# PFC_nano_breakout.net
KiCad netlist of a schematic drawn in EAGLE
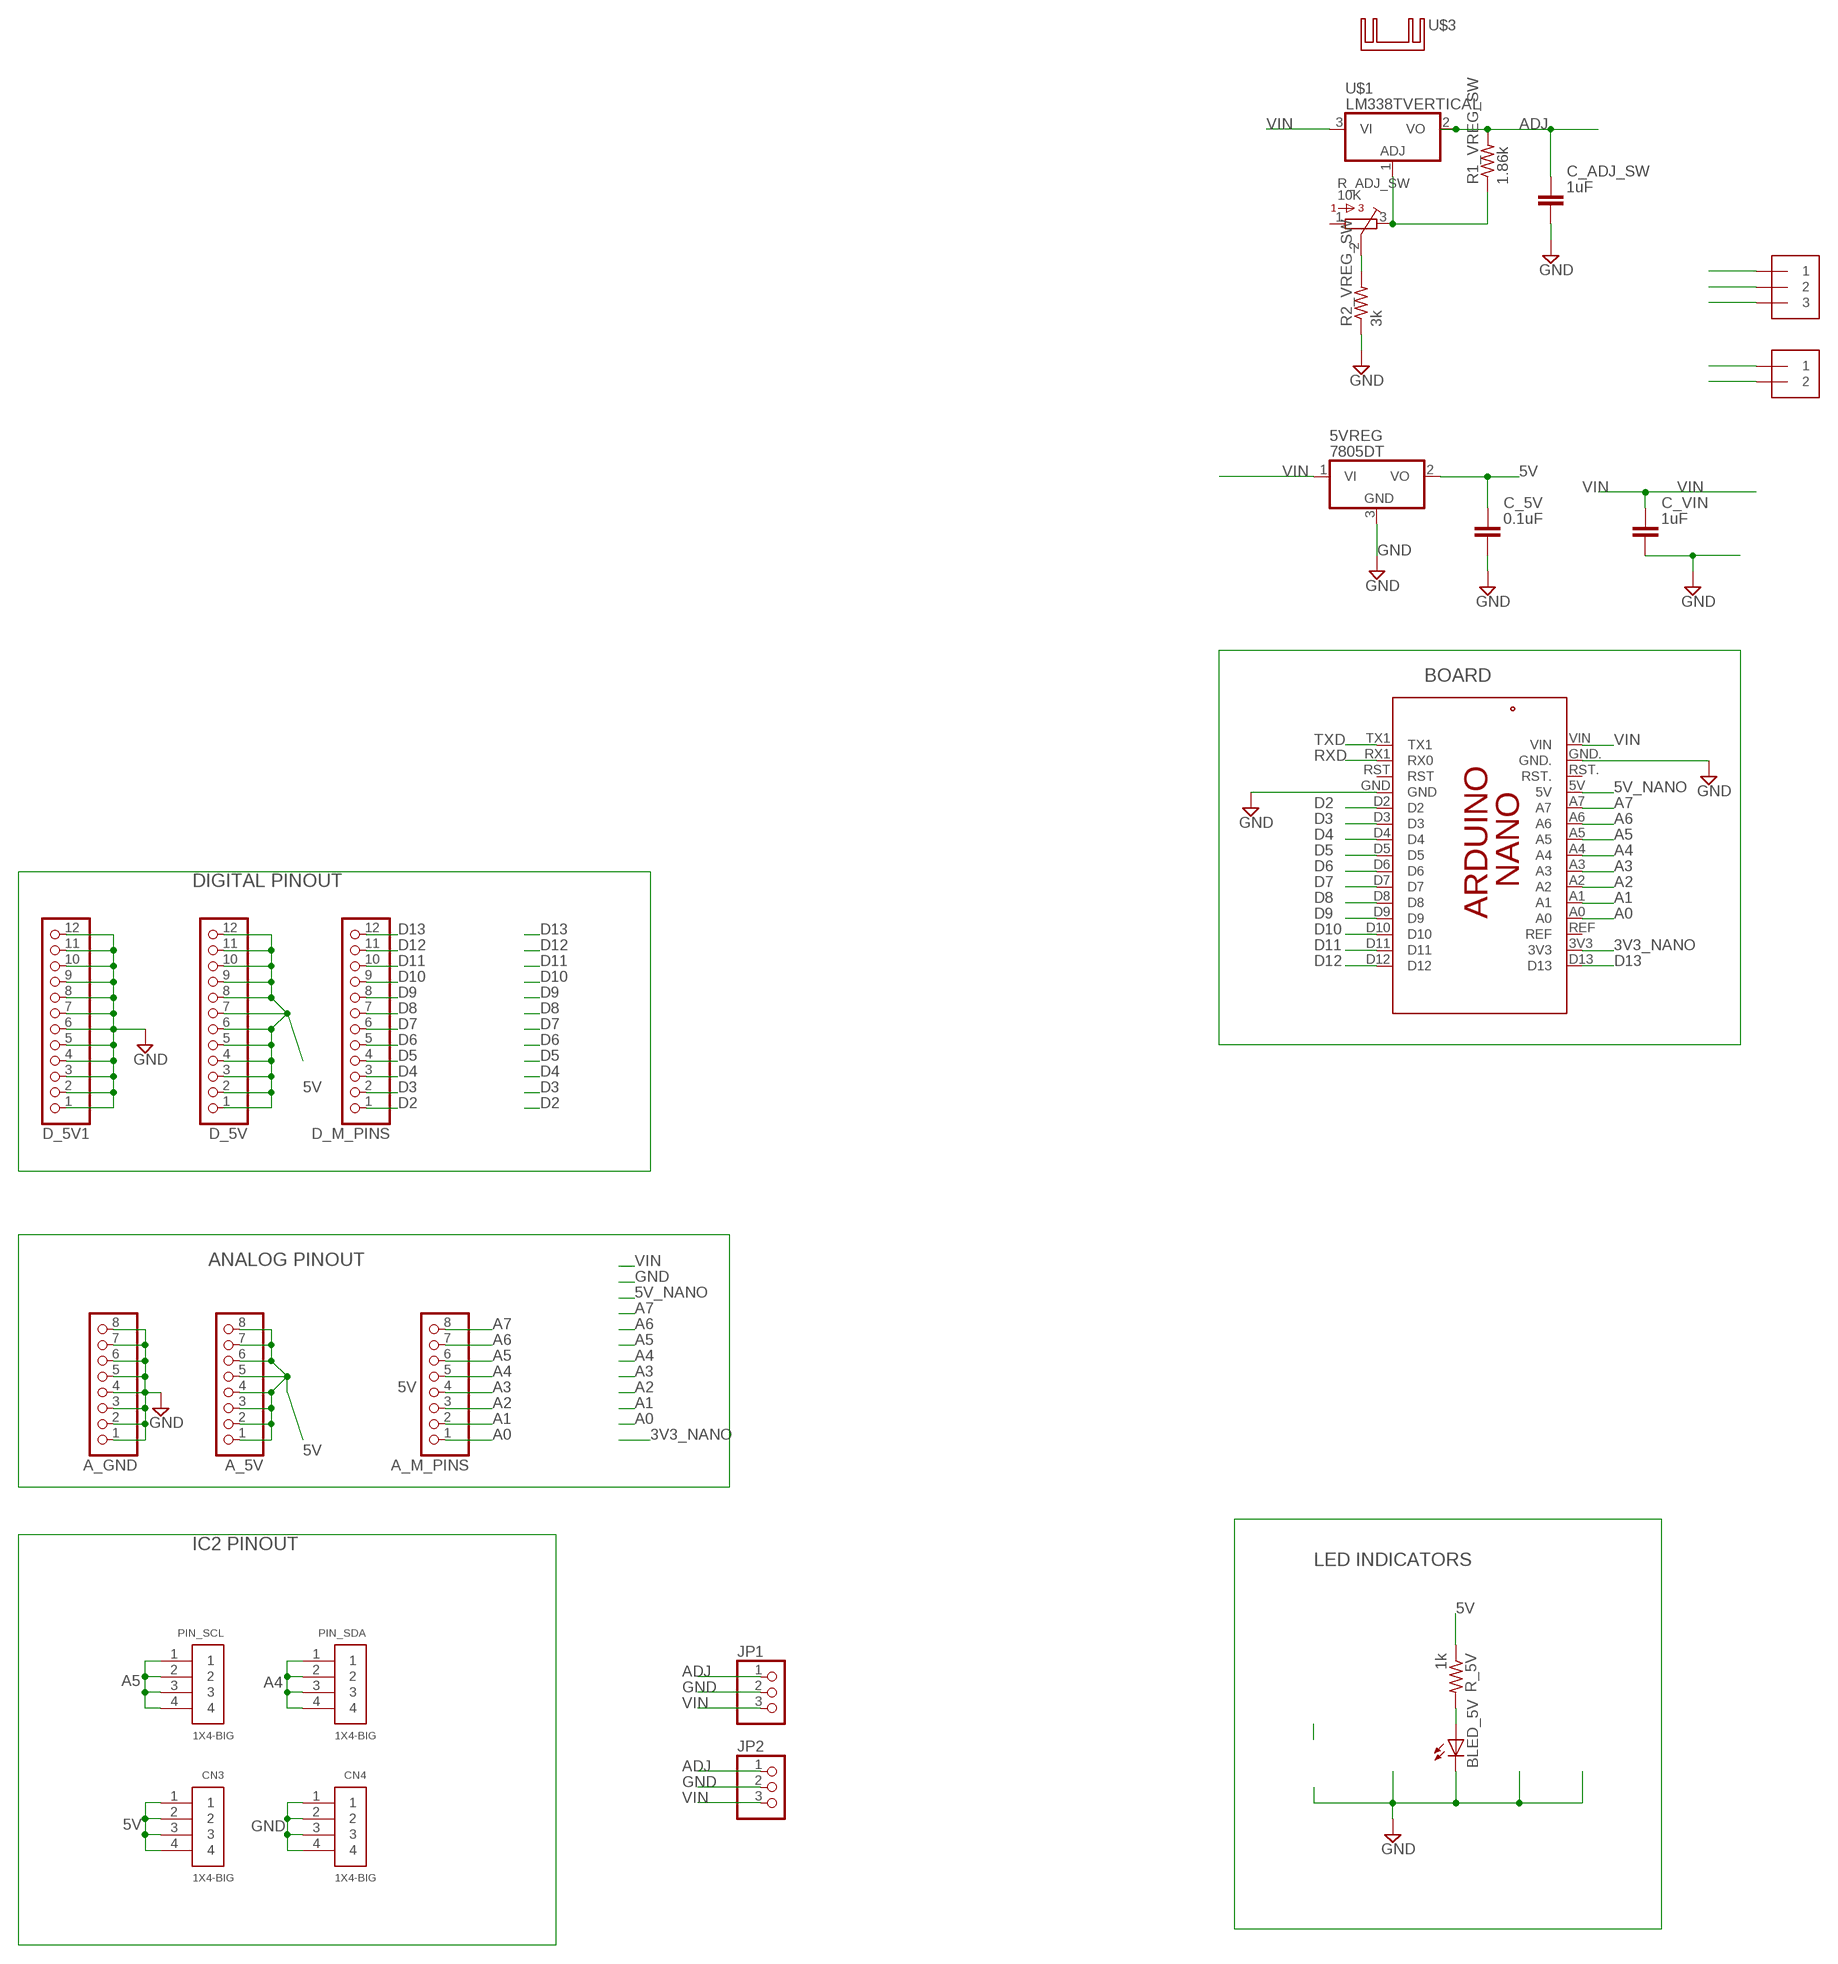
[diagram p0: schematic, sheet 1]

(export (version "E")
  (design (tool "Eeschema 10.0.6"))
  (components
    (comp (ref "5VREG")
      (value "7805DT")
      (footprint "eagle-import:TO252")
      (libsource (lib "eagle-import") (part "78DT05"))
    )
    (comp (ref "A_5V")
      (value "PINHD-1X8CLEANBIG")
      (footprint "eagle-import:1X08-CLEANBIG")
      (libsource (lib "eagle-import") (part "PINHD-1X8CLEANBIG"))
    )
    (comp (ref "A_GND")
      (value "PINHD-1X8CLEANBIG")
      (footprint "eagle-import:1X08-CLEANBIG")
      (libsource (lib "eagle-import") (part "PINHD-1X8CLEANBIG"))
    )
    (comp (ref "A_M_PINS")
      (value "PINHD-1X8CLEANBIG")
      (footprint "eagle-import:1X08-CLEANBIG")
      (libsource (lib "eagle-import") (part "PINHD-1X8CLEANBIG"))
    )
    (comp (ref "BLED_5V")
      (value "LEDCHIP-LED0603")
      (footprint "eagle-import:CHIP-LED0603")
      (libsource (lib "eagle-import") (part "LEDCHIP-LED0603"))
    )
    (comp (ref "CN3")
      (value "1X4-BIG")
      (footprint "eagle-import:1X04-BIG")
      (libsource (lib "eagle-import") (part "1X4-BIG"))
    )
    (comp (ref "CN4")
      (value "1X4-BIG")
      (footprint "eagle-import:1X04-BIG")
      (libsource (lib "eagle-import") (part "1X4-BIG"))
    )
    (comp (ref "C_5V")
      (value "0.1uF")
      (footprint "eagle-import:C603")
      (libsource (lib "eagle-import") (part "CAPACITOR_NPOL-0603"))
    )
    (comp (ref "C_ADJ_SW")
      (value "1uF")
      (footprint "eagle-import:C603")
      (libsource (lib "eagle-import") (part "CAPACITOR_NPOL-0603"))
    )
    (comp (ref "C_VIN")
      (value "1uF")
      (footprint "eagle-import:C603")
      (libsource (lib "eagle-import") (part "CAPACITOR_NPOL-0603"))
    )
    (comp (ref "D_5V")
      (value "PINHD-1X12-CB")
      (footprint "eagle-import:1X12-CB")
      (libsource (lib "eagle-import") (part "PINHD-1X12-CB"))
    )
    (comp (ref "D_5V1")
      (value "PINHD-1X12-CB")
      (footprint "eagle-import:1X12-CB")
      (libsource (lib "eagle-import") (part "PINHD-1X12-CB"))
    )
    (comp (ref "D_M_PINS")
      (value "PINHD-1X12-CB")
      (footprint "eagle-import:1X12-CB")
      (libsource (lib "eagle-import") (part "PINHD-1X12-CB"))
    )
    (comp (ref "J2")
      (value "1X2-3.5MM")
      (footprint "eagle-import:1X2-3.5MM")
      (libsource (lib "eagle-import") (part "1X2-3.5MM"))
    )
    (comp (ref "JP1")
      (value "PINHD-1X3CB")
      (footprint "eagle-import:1X03-CLEANBIG")
      (libsource (lib "eagle-import") (part "PINHD-1X3CB"))
    )
    (comp (ref "JP2")
      (value "PINHD-1X3CB")
      (footprint "eagle-import:1X03-CLEANBIG")
      (libsource (lib "eagle-import") (part "PINHD-1X3CB"))
    )
    (comp (ref "PCB1")
      (value "ARDUINO_NANO_SHIELD")
      (footprint "eagle-import:ARDUINO_NANO_SHIELD")
      (libsource (lib "eagle-import") (part "ARDUINO_NANO_SHIELD"))
    )
    (comp (ref "PIN_SCL")
      (value "1X4-BIG")
      (footprint "eagle-import:1X04-BIG")
      (libsource (lib "eagle-import") (part "1X4-BIG"))
    )
    (comp (ref "PIN_SDA")
      (value "1X4-BIG")
      (footprint "eagle-import:1X04-BIG")
      (libsource (lib "eagle-import") (part "1X4-BIG"))
    )
    (comp (ref "R1_VREG_SW")
      (value "1.86k")
      (footprint "eagle-import:R0603")
      (libsource (lib "eagle-import") (part "R-US_R0603"))
    )
    (comp (ref "R2_VREG_SW")
      (value "3k")
      (footprint "eagle-import:R0603")
      (libsource (lib "eagle-import") (part "R-US_R0603"))
    )
    (comp (ref "R_5V")
      (value "1k")
      (footprint "eagle-import:R0603")
      (libsource (lib "eagle-import") (part "R-US_R0603"))
    )
    (comp (ref "R_ADJ_SW")
      (value "10K")
      (footprint "eagle-import:3386P")
      (libsource (lib "eagle-import") (part "3386-P"))
    )
    (comp (ref "U$1")
      (value "LM338TVERTICAL")
      (footprint "eagle-import:TO220V")
      (libsource (lib "eagle-import") (part "LM338TVERTICAL"))
    )
    (comp (ref "U$2")
      (value "1X3")
      (footprint "eagle-import:1X3-3.5MM")
      (libsource (lib "eagle-import") (part "1X3"))
    )
    (comp (ref "U$3")
      (value "FW1S")
      (footprint "eagle-import:FW1S-DOCU")
      (libsource (lib "eagle-import") (part "FW1S"))
    )
  )
  (nets
    (net (code "1") (name "/3V3_NANO") (class "Default")
      (node (ref "PCB1") (pin "3V3") (pinfunction "3V3_3V3") (pintype "bidirectional"))
    )
    (net (code "2") (name "/5V") (class "Default")
      (node (ref "5VREG") (pin "2") (pinfunction "VO_2") (pintype "passive"))
      (node (ref "A_5V") (pin "1") (pinfunction "1_1") (pintype "passive"))
      (node (ref "A_5V") (pin "2") (pinfunction "2_2") (pintype "passive"))
      (node (ref "A_5V") (pin "3") (pinfunction "3_3") (pintype "passive"))
      (node (ref "A_5V") (pin "4") (pinfunction "4_4") (pintype "passive"))
      (node (ref "A_5V") (pin "5") (pinfunction "5_5") (pintype "passive"))
      (node (ref "A_5V") (pin "6") (pinfunction "6_6") (pintype "passive"))
      (node (ref "A_5V") (pin "7") (pinfunction "7_7") (pintype "passive"))
      (node (ref "A_5V") (pin "8") (pinfunction "8_8") (pintype "passive"))
      (node (ref "CN3") (pin "1") (pinfunction "1_1") (pintype "bidirectional"))
      (node (ref "CN3") (pin "2") (pinfunction "2_2") (pintype "bidirectional"))
      (node (ref "CN3") (pin "3") (pinfunction "3_3") (pintype "bidirectional"))
      (node (ref "CN3") (pin "4") (pinfunction "4_4") (pintype "bidirectional"))
      (node (ref "C_5V") (pin "1") (pinfunction "1_1") (pintype "passive"))
      (node (ref "D_5V") (pin "1") (pinfunction "1_1") (pintype "passive"))
      (node (ref "D_5V") (pin "10") (pinfunction "10_10") (pintype "passive"))
      (node (ref "D_5V") (pin "11") (pinfunction "11_11") (pintype "passive"))
      (node (ref "D_5V") (pin "12") (pinfunction "12_12") (pintype "passive"))
      (node (ref "D_5V") (pin "2") (pinfunction "2_2") (pintype "passive"))
      (node (ref "D_5V") (pin "3") (pinfunction "3_3") (pintype "passive"))
      (node (ref "D_5V") (pin "4") (pinfunction "4_4") (pintype "passive"))
      (node (ref "D_5V") (pin "5") (pinfunction "5_5") (pintype "passive"))
      (node (ref "D_5V") (pin "6") (pinfunction "6_6") (pintype "passive"))
      (node (ref "D_5V") (pin "7") (pinfunction "7_7") (pintype "passive"))
      (node (ref "D_5V") (pin "8") (pinfunction "8_8") (pintype "passive"))
      (node (ref "D_5V") (pin "9") (pinfunction "9_9") (pintype "passive"))
      (node (ref "R_5V") (pin "1") (pinfunction "1_1") (pintype "passive"))
    )
    (net (code "3") (name "/5V_NANO") (class "Default")
      (node (ref "PCB1") (pin "5V") (pinfunction "5V_5V") (pintype "bidirectional"))
    )
    (net (code "4") (name "/A0") (class "Default")
      (node (ref "A_M_PINS") (pin "1") (pinfunction "1_1") (pintype "passive"))
      (node (ref "PCB1") (pin "A0") (pinfunction "A0_A0") (pintype "bidirectional"))
    )
    (net (code "5") (name "/A1") (class "Default")
      (node (ref "A_M_PINS") (pin "2") (pinfunction "2_2") (pintype "passive"))
      (node (ref "PCB1") (pin "A1") (pinfunction "A1_A1") (pintype "bidirectional"))
    )
    (net (code "6") (name "/A2") (class "Default")
      (node (ref "A_M_PINS") (pin "3") (pinfunction "3_3") (pintype "passive"))
      (node (ref "PCB1") (pin "A2") (pinfunction "A2_A2") (pintype "bidirectional"))
    )
    (net (code "7") (name "/A3") (class "Default")
      (node (ref "A_M_PINS") (pin "4") (pinfunction "4_4") (pintype "passive"))
      (node (ref "PCB1") (pin "A3") (pinfunction "A3_A3") (pintype "bidirectional"))
    )
    (net (code "8") (name "/A4") (class "Default")
      (node (ref "A_M_PINS") (pin "5") (pinfunction "5_5") (pintype "passive"))
      (node (ref "PCB1") (pin "A4") (pinfunction "A4_A4") (pintype "bidirectional"))
      (node (ref "PIN_SDA") (pin "1") (pinfunction "1_1") (pintype "bidirectional"))
      (node (ref "PIN_SDA") (pin "2") (pinfunction "2_2") (pintype "bidirectional"))
      (node (ref "PIN_SDA") (pin "3") (pinfunction "3_3") (pintype "bidirectional"))
      (node (ref "PIN_SDA") (pin "4") (pinfunction "4_4") (pintype "bidirectional"))
    )
    (net (code "9") (name "/A5") (class "Default")
      (node (ref "A_M_PINS") (pin "6") (pinfunction "6_6") (pintype "passive"))
      (node (ref "PCB1") (pin "A5") (pinfunction "A5_A5") (pintype "bidirectional"))
      (node (ref "PIN_SCL") (pin "1") (pinfunction "1_1") (pintype "bidirectional"))
      (node (ref "PIN_SCL") (pin "2") (pinfunction "2_2") (pintype "bidirectional"))
      (node (ref "PIN_SCL") (pin "3") (pinfunction "3_3") (pintype "bidirectional"))
      (node (ref "PIN_SCL") (pin "4") (pinfunction "4_4") (pintype "bidirectional"))
    )
    (net (code "10") (name "/A6") (class "Default")
      (node (ref "A_M_PINS") (pin "7") (pinfunction "7_7") (pintype "passive"))
      (node (ref "PCB1") (pin "A6") (pinfunction "A6_A6") (pintype "bidirectional"))
    )
    (net (code "11") (name "/A7") (class "Default")
      (node (ref "A_M_PINS") (pin "8") (pinfunction "8_8") (pintype "passive"))
      (node (ref "PCB1") (pin "A7") (pinfunction "A7_A7") (pintype "bidirectional"))
    )
    (net (code "12") (name "/ADJ") (class "Default")
      (node (ref "C_ADJ_SW") (pin "1") (pinfunction "1_1") (pintype "passive"))
      (node (ref "JP1") (pin "1") (pinfunction "1_1") (pintype "passive"))
      (node (ref "JP2") (pin "1") (pinfunction "1_1") (pintype "passive"))
      (node (ref "R1_VREG_SW") (pin "2") (pinfunction "2_2") (pintype "passive"))
      (node (ref "U$1") (pin "2") (pinfunction "VO_2") (pintype "passive"))
      (node (ref "U$2") (pin "2") (pinfunction "2_2") (pintype "passive"))
    )
    (net (code "13") (name "/D2") (class "Default")
      (node (ref "D_M_PINS") (pin "1") (pinfunction "1_1") (pintype "passive"))
      (node (ref "PCB1") (pin "D2") (pinfunction "D2_D2") (pintype "bidirectional"))
    )
    (net (code "14") (name "/D3") (class "Default")
      (node (ref "D_M_PINS") (pin "2") (pinfunction "2_2") (pintype "passive"))
      (node (ref "PCB1") (pin "D3") (pinfunction "D3_D3") (pintype "bidirectional"))
    )
    (net (code "15") (name "/D4") (class "Default")
      (node (ref "D_M_PINS") (pin "3") (pinfunction "3_3") (pintype "passive"))
      (node (ref "PCB1") (pin "D4") (pinfunction "D4_D4") (pintype "bidirectional"))
    )
    (net (code "16") (name "/D5") (class "Default")
      (node (ref "D_M_PINS") (pin "4") (pinfunction "4_4") (pintype "passive"))
      (node (ref "PCB1") (pin "D5") (pinfunction "D5_D5") (pintype "bidirectional"))
    )
    (net (code "17") (name "/D6") (class "Default")
      (node (ref "D_M_PINS") (pin "5") (pinfunction "5_5") (pintype "passive"))
      (node (ref "PCB1") (pin "D6") (pinfunction "D6_D6") (pintype "bidirectional"))
    )
    (net (code "18") (name "/D7") (class "Default")
      (node (ref "D_M_PINS") (pin "6") (pinfunction "6_6") (pintype "passive"))
      (node (ref "PCB1") (pin "D7") (pinfunction "D7_D7") (pintype "bidirectional"))
    )
    (net (code "19") (name "/D8") (class "Default")
      (node (ref "D_M_PINS") (pin "7") (pinfunction "7_7") (pintype "passive"))
      (node (ref "PCB1") (pin "D8") (pinfunction "D8_D8") (pintype "bidirectional"))
    )
    (net (code "20") (name "/D9") (class "Default")
      (node (ref "D_M_PINS") (pin "8") (pinfunction "8_8") (pintype "passive"))
      (node (ref "PCB1") (pin "D9") (pinfunction "D9_D9") (pintype "bidirectional"))
    )
    (net (code "21") (name "/D10") (class "Default")
      (node (ref "D_M_PINS") (pin "9") (pinfunction "9_9") (pintype "passive"))
      (node (ref "PCB1") (pin "D10") (pinfunction "D10_D10") (pintype "bidirectional"))
    )
    (net (code "22") (name "/D11") (class "Default")
      (node (ref "D_M_PINS") (pin "10") (pinfunction "10_10") (pintype "passive"))
      (node (ref "PCB1") (pin "D11") (pinfunction "D11_D11") (pintype "bidirectional"))
    )
    (net (code "23") (name "/D12") (class "Default")
      (node (ref "D_M_PINS") (pin "11") (pinfunction "11_11") (pintype "passive"))
      (node (ref "PCB1") (pin "D12") (pinfunction "D12_D12") (pintype "bidirectional"))
    )
    (net (code "24") (name "/D13") (class "Default")
      (node (ref "D_M_PINS") (pin "12") (pinfunction "12_12") (pintype "passive"))
      (node (ref "PCB1") (pin "D13") (pinfunction "D13_D13") (pintype "bidirectional"))
    )
    (net (code "25") (name "/RXD") (class "Default")
      (node (ref "PCB1") (pin "RX1") (pinfunction "RX0_RX1") (pintype "bidirectional"))
    )
    (net (code "26") (name "/TXD") (class "Default")
      (node (ref "PCB1") (pin "TX1") (pinfunction "TX1_TX1") (pintype "bidirectional"))
    )
    (net (code "27") (name "/VIN") (class "Default")
      (node (ref "5VREG") (pin "1") (pinfunction "VI_1") (pintype "input"))
      (node (ref "C_VIN") (pin "1") (pinfunction "1_1") (pintype "passive"))
      (node (ref "J2") (pin "2") (pinfunction "2_2") (pintype "passive"))
      (node (ref "JP1") (pin "3") (pinfunction "3_3") (pintype "passive"))
      (node (ref "JP2") (pin "3") (pinfunction "3_3") (pintype "passive"))
      (node (ref "PCB1") (pin "VIN") (pinfunction "VIN_VIN") (pintype "bidirectional"))
      (node (ref "U$1") (pin "3") (pinfunction "VI_3") (pintype "input"))
      (node (ref "U$2") (pin "3") (pinfunction "3_3") (pintype "passive"))
    )
    (net (code "28") (name "GND") (class "Default")
      (node (ref "5VREG") (pin "3") (pinfunction "GND_3") (pintype "passive"))
      (node (ref "A_GND") (pin "1") (pinfunction "1_1") (pintype "passive"))
      (node (ref "A_GND") (pin "2") (pinfunction "2_2") (pintype "passive"))
      (node (ref "A_GND") (pin "3") (pinfunction "3_3") (pintype "passive"))
      (node (ref "A_GND") (pin "4") (pinfunction "4_4") (pintype "passive"))
      (node (ref "A_GND") (pin "5") (pinfunction "5_5") (pintype "passive"))
      (node (ref "A_GND") (pin "6") (pinfunction "6_6") (pintype "passive"))
      (node (ref "A_GND") (pin "7") (pinfunction "7_7") (pintype "passive"))
      (node (ref "A_GND") (pin "8") (pinfunction "8_8") (pintype "passive"))
      (node (ref "BLED_5V") (pin "C") (pinfunction "C_C") (pintype "passive"))
      (node (ref "CN4") (pin "1") (pinfunction "1_1") (pintype "bidirectional"))
      (node (ref "CN4") (pin "2") (pinfunction "2_2") (pintype "bidirectional"))
      (node (ref "CN4") (pin "3") (pinfunction "3_3") (pintype "bidirectional"))
      (node (ref "CN4") (pin "4") (pinfunction "4_4") (pintype "bidirectional"))
      (node (ref "C_5V") (pin "2") (pinfunction "2_2") (pintype "passive"))
      (node (ref "C_ADJ_SW") (pin "2") (pinfunction "2_2") (pintype "passive"))
      (node (ref "C_VIN") (pin "2") (pinfunction "2_2") (pintype "passive"))
      (node (ref "D_5V1") (pin "1") (pinfunction "1_1") (pintype "passive"))
      (node (ref "D_5V1") (pin "10") (pinfunction "10_10") (pintype "passive"))
      (node (ref "D_5V1") (pin "11") (pinfunction "11_11") (pintype "passive"))
      (node (ref "D_5V1") (pin "12") (pinfunction "12_12") (pintype "passive"))
      (node (ref "D_5V1") (pin "2") (pinfunction "2_2") (pintype "passive"))
      (node (ref "D_5V1") (pin "3") (pinfunction "3_3") (pintype "passive"))
      (node (ref "D_5V1") (pin "4") (pinfunction "4_4") (pintype "passive"))
      (node (ref "D_5V1") (pin "5") (pinfunction "5_5") (pintype "passive"))
      (node (ref "D_5V1") (pin "6") (pinfunction "6_6") (pintype "passive"))
      (node (ref "D_5V1") (pin "7") (pinfunction "7_7") (pintype "passive"))
      (node (ref "D_5V1") (pin "8") (pinfunction "8_8") (pintype "passive"))
      (node (ref "D_5V1") (pin "9") (pinfunction "9_9") (pintype "passive"))
      (node (ref "J2") (pin "1") (pinfunction "1_1") (pintype "passive"))
      (node (ref "JP1") (pin "2") (pinfunction "2_2") (pintype "passive"))
      (node (ref "JP2") (pin "2") (pinfunction "2_2") (pintype "passive"))
      (node (ref "PCB1") (pin "GND") (pinfunction "GND_GND") (pintype "bidirectional"))
      (node (ref "PCB1") (pin "GND.") (pinfunction "GND._GND.") (pintype "bidirectional"))
      (node (ref "R2_VREG_SW") (pin "1") (pinfunction "1_1") (pintype "passive"))
      (node (ref "U$2") (pin "1") (pinfunction "1_1") (pintype "passive"))
    )
    (net (code "29") (name "Net-(BLED_5V-PadA)") (class "Default")
      (node (ref "BLED_5V") (pin "A") (pinfunction "A_A") (pintype "passive"))
      (node (ref "R_5V") (pin "2") (pinfunction "2_2") (pintype "passive"))
    )
    (net (code "30") (name "Net-(R2_VREG_SW-Pad2)") (class "Default")
      (node (ref "R2_VREG_SW") (pin "2") (pinfunction "2_2") (pintype "passive"))
      (node (ref "R_ADJ_SW") (pin "2") (pinfunction "2_2") (pintype "passive"))
    )
    (net (code "31") (name "Net-(U$1-GND)") (class "Default")
      (node (ref "R1_VREG_SW") (pin "1") (pinfunction "1_1") (pintype "passive"))
      (node (ref "R_ADJ_SW") (pin "3") (pinfunction "3_3") (pintype "passive"))
      (node (ref "U$1") (pin "1") (pinfunction "GND_1") (pintype "passive"))
    )
    (net (code "32") (name "unconnected-(PCB1-PadREF)") (class "Default")
      (node (ref "PCB1") (pin "REF") (pinfunction "REF_REF") (pintype "bidirectional"))
    )
    (net (code "33") (name "unconnected-(PCB1-PadRST)") (class "Default")
      (node (ref "PCB1") (pin "RST") (pinfunction "RST_RST") (pintype "bidirectional"))
    )
    (net (code "34") (name "unconnected-(PCB1-PadRST.)") (class "Default")
      (node (ref "PCB1") (pin "RST.") (pinfunction "RST._RST.") (pintype "bidirectional"))
    )
    (net (code "35") (name "unconnected-(R_ADJ_SW-Pad1)") (class "Default")
      (node (ref "R_ADJ_SW") (pin "1") (pinfunction "1_1") (pintype "passive"))
    )
  )
)
